# smoothieboard-alt-p2.net
KiCad netlist of a schematic drawn in Altium Designer
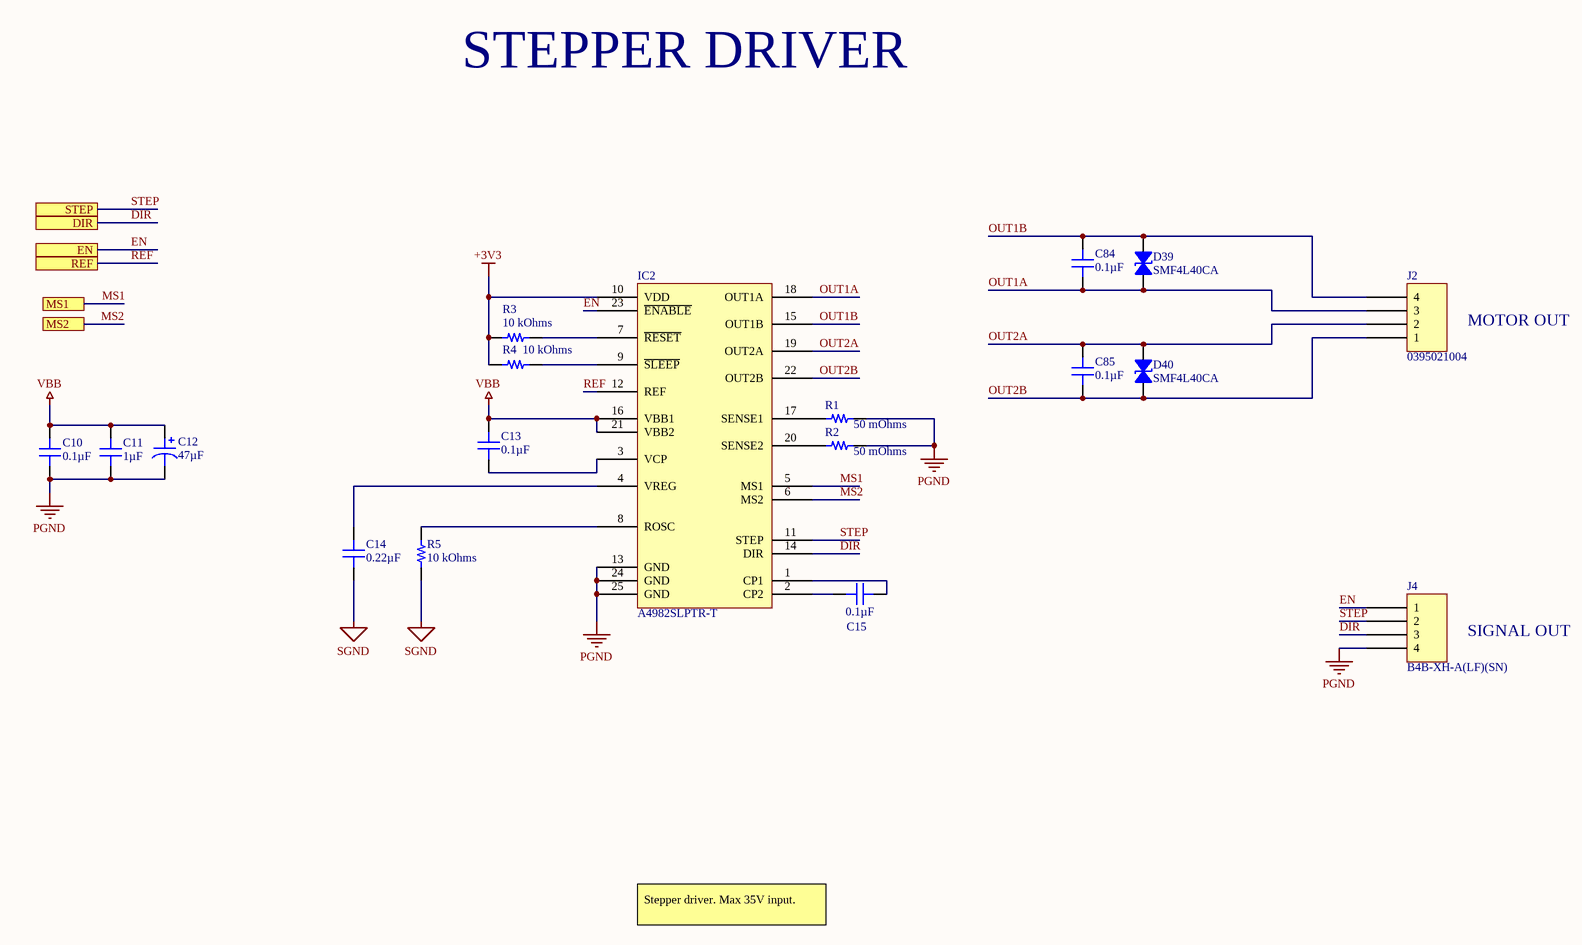
[diagram p0: smoothieboard-alt-p2.SchDoc]

(export (version "E")
  (design (tool "Eeschema 10.0.6"))
  (components
    (comp (ref "C10")
      (value "0.1µF")
      (footprint "CAP 0603_1608")
      (description "CAP CER 0.1UF 50V X7R 0603")
      (fields (field (name "PART NUMBER") "C0603C104K5RAC7411") (field (name "MANUFACTURER") "KEMET"))
      (libsource (lib "CAL") (part "Capacitor"))
    )
    (comp (ref "C11")
      (value "1µF")
      (footprint "CAP 0603_1608")
      (description "CAP CER 1UF 50V X5R 0603")
      (fields (field (name "PART NUMBER") "UMK107ABJ105MAHT") (field (name "MANUFACTURER") "Taiyo Yuden"))
      (libsource (lib "CAL") (part "Capacitor"))
    )
    (comp (ref "C12")
      (value "47µF")
      (footprint "CAP ALSMD 8.3MM H10.5MM")
      (description "CAP ALUM 47UF 20% 63V SMD")
      (fields (field (name "PART NUMBER") "63SEV47M8X10.5") (field (name "MANUFACTURER") "Rubycon"))
      (libsource (lib "CAL") (part "Polarised Capacitor"))
    )
    (comp (ref "C13")
      (value "0.1µF")
      (footprint "CAP 0402_1005")
      (description "CAP CER 0.1UF 35V X5R 0402")
      (fields
        (field (name "PART NUMBER") "CGA2B3X5R1V104K050BB")
        (field (name "MANUFACTURER") "TDK Corporation")
      )
      (libsource (lib "CAL") (part "Capacitor"))
    )
    (comp (ref "C14")
      (value "0.22µF")
      (footprint "CAP 0603_1608")
      (description "CAP CER 0.22UF 10V X7R 0603")
      (fields (field (name "PART NUMBER") "CC0603MRX7R6BB224") (field (name "MANUFACTURER") "Yageo"))
      (libsource (lib "CAL") (part "Capacitor"))
    )
    (comp (ref "C15")
      (value "0.1µF")
      (footprint "CAP 0402_1005")
      (description "CAP CER 0.1UF 35V X5R 0402")
      (fields
        (field (name "PART NUMBER") "CGA2B3X5R1V104K050BB")
        (field (name "MANUFACTURER") "TDK Corporation")
      )
      (libsource (lib "CAL") (part "Capacitor"))
    )
    (comp (ref "C84")
      (value "0.1µF")
      (footprint "CAP 0402_1005")
      (description "CAP CER 0.1UF 35V X5R 0402")
      (fields
        (field (name "PART NUMBER") "CGA2B3X5R1V104K050BB")
        (field (name "MANUFACTURER") "TDK Corporation")
      )
      (libsource (lib "CAL") (part "Capacitor"))
    )
    (comp (ref "C85")
      (value "0.1µF")
      (footprint "CAP 0402_1005")
      (description "CAP CER 0.1UF 35V X5R 0402")
      (fields
        (field (name "PART NUMBER") "CGA2B3X5R1V104K050BB")
        (field (name "MANUFACTURER") "TDK Corporation")
      )
      (libsource (lib "CAL") (part "Capacitor"))
    )
    (comp (ref "D39")
      (value "SMF4L40CA")
      (footprint "SOD123F")
      (description "TVS DIODE SMF4L 40V BI 400W")
      (fields (field (name "MANUFACTURER") "Littelfuse Inc."))
      (libsource (lib "CAL") (part "Diode TVS"))
    )
    (comp (ref "D40")
      (value "SMF4L40CA")
      (footprint "SOD123F")
      (description "TVS DIODE SMF4L 40V BI 400W")
      (fields (field (name "MANUFACTURER") "Littelfuse Inc."))
      (libsource (lib "CAL") (part "Diode TVS"))
    )
    (comp (ref "IC2")
      (value "A4982SLPTR-T")
      (footprint "ALLEGRO TSSOP-24 LP")
      (description "IC MTR DRV BIPOLR 3-5.5V 24TSSOP")
      (fields (field (name "MANUFACTURER") "Allegro MicroSystems"))
      (libsource (lib "CAL") (part "Allegro A4982 24Pin"))
    )
    (comp (ref "J2")
      (value "0395021004")
      (footprint "MOLEX 395021004")
      (description "TERM BLOCK HDR 4POS 90DEG 3.5MM")
      (fields (field (name "MANUFACTURER") "Molex"))
      (libsource (lib "CAL") (part "4 Pin"))
    )
    (comp (ref "J4")
      (value "B4B-XH-A(LF)(SN)")
      (footprint "JST XH B4B-XH-A")
      (description "CONN HEADER VERT 4POS 2.5MM")
      (fields (field (name "MANUFACTURER") "JST Sales America Inc."))
      (libsource (lib "") (part "4 Pin_1"))
    )
    (comp (ref "R1")
      (value "50 mOhms")
      (footprint "RES 2512_6432")
      (description "RES 0.05 OHM 0.1% 1W 2512")
      (fields
        (field (name "PART NUMBER") "Y14870R05000B9W")
        (field (name "MANUFACTURER") "Vishay Foil Resistors (Division of Vishay Precision Group)")
      )
      (libsource (lib "CAL") (part "Resistor"))
    )
    (comp (ref "R2")
      (value "50 mOhms")
      (footprint "RES 2512_6432")
      (description "RES 0.05 OHM 0.1% 1W 2512")
      (fields
        (field (name "PART NUMBER") "Y14870R05000B9W")
        (field (name "MANUFACTURER") "Vishay Foil Resistors (Division of Vishay Precision Group)")
      )
      (libsource (lib "CAL") (part "Resistor"))
    )
    (comp (ref "R3")
      (value "10 kOhms")
      (footprint "RES 0402_1005")
      (description "RES SMD 10K OHM 5% 1/16W 0402")
      (fields (field (name "PART NUMBER") "CRCW040210K0JNTD") (field (name "MANUFACTURER") "Vishay Dale"))
      (libsource (lib "CAL") (part "Resistor"))
    )
    (comp (ref "R4")
      (value "10 kOhms")
      (footprint "RES 0402_1005")
      (description "RES SMD 10K OHM 5% 1/16W 0402")
      (fields (field (name "PART NUMBER") "CRCW040210K0JNTD") (field (name "MANUFACTURER") "Vishay Dale"))
      (libsource (lib "CAL") (part "Resistor"))
    )
    (comp (ref "R5")
      (value "10 kOhms")
      (footprint "RES 0402_1005")
      (description "RES SMD 10K OHM 5% 1/16W 0402")
      (fields (field (name "PART NUMBER") "CRCW040210K0JNTD") (field (name "MANUFACTURER") "Vishay Dale"))
      (libsource (lib "CAL") (part "Resistor"))
    )
  )
  (nets
    (net (code "1") (name "+3V3") (class "Default")
      (node (ref "IC2") (pin "10") (pinfunction "VDD_10") (pintype "passive"))
      (node (ref "R3") (pin "2") (pinfunction "2_2") (pintype "passive"))
      (node (ref "R4") (pin "2") (pinfunction "2_2") (pintype "passive"))
    )
    (net (code "2") (name "/DIR") (class "Default")
      (node (ref "IC2") (pin "14") (pinfunction "DIR_14") (pintype "passive"))
      (node (ref "J4") (pin "3") (pinfunction "3_3") (pintype "passive"))
    )
    (net (code "3") (name "/EN") (class "Default")
      (node (ref "IC2") (pin "23") (pinfunction "~{ENABLE}_23") (pintype "passive"))
      (node (ref "J4") (pin "1") (pinfunction "1_1") (pintype "passive"))
    )
    (net (code "4") (name "/MS1") (class "Default")
      (node (ref "IC2") (pin "5") (pinfunction "MS1_5") (pintype "passive"))
    )
    (net (code "5") (name "/MS2") (class "Default")
      (node (ref "IC2") (pin "6") (pinfunction "MS2_6") (pintype "passive"))
    )
    (net (code "6") (name "/OUT1A") (class "Default")
      (node (ref "C84") (pin "1") (pinfunction "1_1") (pintype "passive"))
      (node (ref "D39") (pin "1") (pinfunction "1_1") (pintype "passive"))
      (node (ref "IC2") (pin "18") (pinfunction "OUT1A_18") (pintype "passive"))
      (node (ref "J2") (pin "3") (pinfunction "3_3") (pintype "passive"))
    )
    (net (code "7") (name "/OUT1B") (class "Default")
      (node (ref "C84") (pin "2") (pinfunction "2_2") (pintype "passive"))
      (node (ref "D39") (pin "2") (pinfunction "2_2") (pintype "passive"))
      (node (ref "IC2") (pin "15") (pinfunction "OUT1B_15") (pintype "passive"))
      (node (ref "J2") (pin "4") (pinfunction "4_4") (pintype "passive"))
    )
    (net (code "8") (name "/OUT2A") (class "Default")
      (node (ref "C85") (pin "2") (pinfunction "2_2") (pintype "passive"))
      (node (ref "D40") (pin "2") (pinfunction "2_2") (pintype "passive"))
      (node (ref "IC2") (pin "19") (pinfunction "OUT2A_19") (pintype "passive"))
      (node (ref "J2") (pin "2") (pinfunction "2_2") (pintype "passive"))
    )
    (net (code "9") (name "/OUT2B") (class "Default")
      (node (ref "C85") (pin "1") (pinfunction "1_1") (pintype "passive"))
      (node (ref "D40") (pin "1") (pinfunction "1_1") (pintype "passive"))
      (node (ref "IC2") (pin "22") (pinfunction "OUT2B_22") (pintype "passive"))
      (node (ref "J2") (pin "1") (pinfunction "1_1") (pintype "passive"))
    )
    (net (code "10") (name "/REF") (class "Default")
      (node (ref "IC2") (pin "12") (pinfunction "REF_12") (pintype "passive"))
    )
    (net (code "11") (name "/STEP") (class "Default")
      (node (ref "IC2") (pin "11") (pinfunction "STEP_11") (pintype "passive"))
      (node (ref "J4") (pin "2") (pinfunction "2_2") (pintype "passive"))
    )
    (net (code "12") (name "Net-(IC2-CP1)") (class "Default")
      (node (ref "C15") (pin "2") (pinfunction "2_2") (pintype "passive"))
      (node (ref "IC2") (pin "1") (pinfunction "CP1_1") (pintype "passive"))
    )
    (net (code "13") (name "Net-(IC2-CP2)") (class "Default")
      (node (ref "C15") (pin "1") (pinfunction "1_1") (pintype "passive"))
      (node (ref "IC2") (pin "2") (pinfunction "CP2_2") (pintype "passive"))
    )
    (net (code "14") (name "Net-(IC2-ROSC)") (class "Default")
      (node (ref "IC2") (pin "8") (pinfunction "ROSC_8") (pintype "passive"))
      (node (ref "R5") (pin "1") (pinfunction "1_1") (pintype "passive"))
    )
    (net (code "15") (name "Net-(IC2-SENSE1)") (class "Default")
      (node (ref "IC2") (pin "17") (pinfunction "SENSE1_17") (pintype "passive"))
      (node (ref "R1") (pin "1") (pinfunction "1_1") (pintype "passive"))
    )
    (net (code "16") (name "Net-(IC2-SENSE2)") (class "Default")
      (node (ref "IC2") (pin "20") (pinfunction "SENSE2_20") (pintype "passive"))
      (node (ref "R2") (pin "1") (pinfunction "1_1") (pintype "passive"))
    )
    (net (code "17") (name "Net-(IC2-VCP)") (class "Default")
      (node (ref "C13") (pin "1") (pinfunction "1_1") (pintype "passive"))
      (node (ref "IC2") (pin "3") (pinfunction "VCP_3") (pintype "passive"))
    )
    (net (code "18") (name "Net-(IC2-VREG)") (class "Default")
      (node (ref "C14") (pin "2") (pinfunction "2_2") (pintype "passive"))
      (node (ref "IC2") (pin "4") (pinfunction "VREG_4") (pintype "passive"))
    )
    (net (code "19") (name "Net-(IC2-~{RESET})") (class "Default")
      (node (ref "IC2") (pin "7") (pinfunction "~{RESET}_7") (pintype "passive"))
      (node (ref "R3") (pin "1") (pinfunction "1_1") (pintype "passive"))
    )
    (net (code "20") (name "Net-(IC2-~{SLEEP})") (class "Default")
      (node (ref "IC2") (pin "9") (pinfunction "~{SLEEP}_9") (pintype "passive"))
      (node (ref "R4") (pin "1") (pinfunction "1_1") (pintype "passive"))
    )
    (net (code "21") (name "PGND") (class "Default")
      (node (ref "C10") (pin "1") (pinfunction "1_1") (pintype "passive"))
      (node (ref "C11") (pin "1") (pinfunction "1_1") (pintype "passive"))
      (node (ref "C12") (pin "2") (pinfunction "2_2") (pintype "passive"))
      (node (ref "IC2") (pin "13") (pinfunction "GND_13") (pintype "passive"))
      (node (ref "IC2") (pin "24") (pinfunction "GND_24") (pintype "passive"))
      (node (ref "IC2") (pin "25") (pinfunction "GND_25") (pintype "passive"))
      (node (ref "J4") (pin "4") (pinfunction "4_4") (pintype "passive"))
      (node (ref "R1") (pin "2") (pinfunction "2_2") (pintype "passive"))
      (node (ref "R2") (pin "2") (pinfunction "2_2") (pintype "passive"))
    )
    (net (code "22") (name "SGND") (class "Default")
      (node (ref "C14") (pin "1") (pinfunction "1_1") (pintype "passive"))
      (node (ref "R5") (pin "2") (pinfunction "2_2") (pintype "passive"))
    )
    (net (code "23") (name "VBB") (class "Default")
      (node (ref "C10") (pin "2") (pinfunction "2_2") (pintype "passive"))
      (node (ref "C11") (pin "2") (pinfunction "2_2") (pintype "passive"))
      (node (ref "C12") (pin "1") (pinfunction "1_1") (pintype "passive"))
      (node (ref "C13") (pin "2") (pinfunction "2_2") (pintype "passive"))
      (node (ref "IC2") (pin "16") (pinfunction "VBB1_16") (pintype "passive"))
      (node (ref "IC2") (pin "21") (pinfunction "VBB2_21") (pintype "passive"))
    )
  )
)
